# plant_reminder.net
KiCad netlist of a schematic drawn in EAGLE
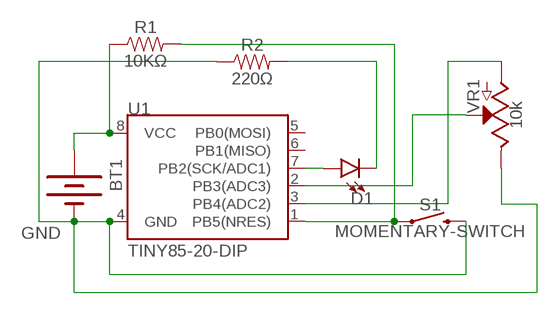
[diagram p0: schematic, sheet 1]

(export (version "E")
  (design (tool "Eeschema 10.0.6"))
  (components
    (comp (ref "BT1")
      (value "BATTERYFOB")
      (footprint "eagle-import:BATTERY_20MM_PTH_COMPACT")
      (libsource (lib "eagle-import") (part "BATTERYFOB"))
    )
    (comp (ref "D1")
      (value "LED5MM-KIT")
      (footprint "eagle-import:LED_5MM-KIT")
      (libsource (lib "eagle-import") (part "LED5MM-KIT"))
    )
    (comp (ref "R1")
      (value "10KΩ")
      (footprint "eagle-import:AXIAL-0.3")
      (libsource (lib "eagle-import") (part "10OHM-HORIZ-1/4W-1%"))
    )
    (comp (ref "R2")
      (value "220Ω")
      (footprint "eagle-import:AXIAL-0.3")
      (libsource (lib "eagle-import") (part "RESISTORAXIAL-0.3"))
    )
    (comp (ref "S1")
      (value "MOMENTARY-SWITCH")
      (footprint "eagle-import:TACTILE_SWITCH_PTH_6.0MM")
      (libsource (lib "eagle-import") (part "MOMENTARY-SWITCH-SPST-PTH-6.0MM"))
    )
    (comp (ref "U1")
      (value "TINY85-20-DIP")
      (footprint "eagle-import:DIP08_MCU")
      (libsource (lib "eagle-import") (part "ATTINY45TINY85-20-DIP"))
    )
    (comp (ref "VR1")
      (value "10k")
      (footprint "eagle-import:POT-PTH-ALPS-KIT")
      (libsource (lib "eagle-import") (part "POTENTIOMETER-PTH-9MM-1/20W-20%-KIT"))
    )
  )
  (nets
    (net (code "1") (name "/GND") (class "Default")
      (node (ref "BT1") (pin "2") (pinfunction "-_2") (pintype "power_in"))
      (node (ref "R2") (pin "P$1") (pinfunction "1_P$1") (pintype "passive"))
      (node (ref "S1") (pin "3") (pinfunction "2_3") (pintype "passive"))
      (node (ref "U1") (pin "4") (pinfunction "GND_4") (pintype "bidirectional"))
      (node (ref "VR1") (pin "P$1") (pinfunction "E_P$1") (pintype "passive"))
    )
    (net (code "2") (name "Net-(BT1-+)") (class "Default")
      (node (ref "BT1") (pin "1") (pinfunction "+_1") (pintype "power_in"))
      (node (ref "R1") (pin "P$1") (pinfunction "1_P$1") (pintype "passive"))
      (node (ref "U1") (pin "8") (pinfunction "VCC_8") (pintype "bidirectional"))
    )
    (net (code "3") (name "Net-(D1-C)") (class "Default")
      (node (ref "D1") (pin "K") (pinfunction "C_K") (pintype "passive"))
      (node (ref "R2") (pin "P$2") (pinfunction "2_P$2") (pintype "passive"))
    )
    (net (code "4") (name "Net-(R1-2)") (class "Default")
      (node (ref "R1") (pin "P$2") (pinfunction "2_P$2") (pintype "passive"))
      (node (ref "S1") (pin "1") (pinfunction "1_1") (pintype "passive"))
      (node (ref "U1") (pin "1") (pinfunction "PB5(NRES)_1") (pintype "bidirectional"))
    )
    (net (code "5") (name "Net-(U1-PB2(SCK{slash}ADC1))") (class "Default")
      (node (ref "D1") (pin "A") (pinfunction "A_A") (pintype "passive"))
      (node (ref "U1") (pin "7") (pinfunction "PB2(SCK/ADC1)_7") (pintype "bidirectional"))
    )
    (net (code "6") (name "Net-(U1-PB3(ADC3))") (class "Default")
      (node (ref "U1") (pin "2") (pinfunction "PB3(ADC3)_2") (pintype "bidirectional"))
      (node (ref "VR1") (pin "P$2") (pinfunction "S_P$2") (pintype "passive"))
    )
    (net (code "7") (name "Net-(U1-PB4(ADC2))") (class "Default")
      (node (ref "U1") (pin "3") (pinfunction "PB4(ADC2)_3") (pintype "bidirectional"))
      (node (ref "VR1") (pin "P$3") (pinfunction "A_P$3") (pintype "passive"))
    )
    (net (code "8") (name "unconnected-(U1-PB0(MOSI)-Pad5)") (class "Default")
      (node (ref "U1") (pin "5") (pinfunction "PB0(MOSI)_5") (pintype "bidirectional"))
    )
    (net (code "9") (name "unconnected-(U1-PB1(MISO)-Pad6)") (class "Default")
      (node (ref "U1") (pin "6") (pinfunction "PB1(MISO)_6") (pintype "bidirectional"))
    )
  )
)
